# SCH_Line_Following_Robot_PCB_2023-12-15.net
KiCad netlist of a schematic drawn in EasyEDA
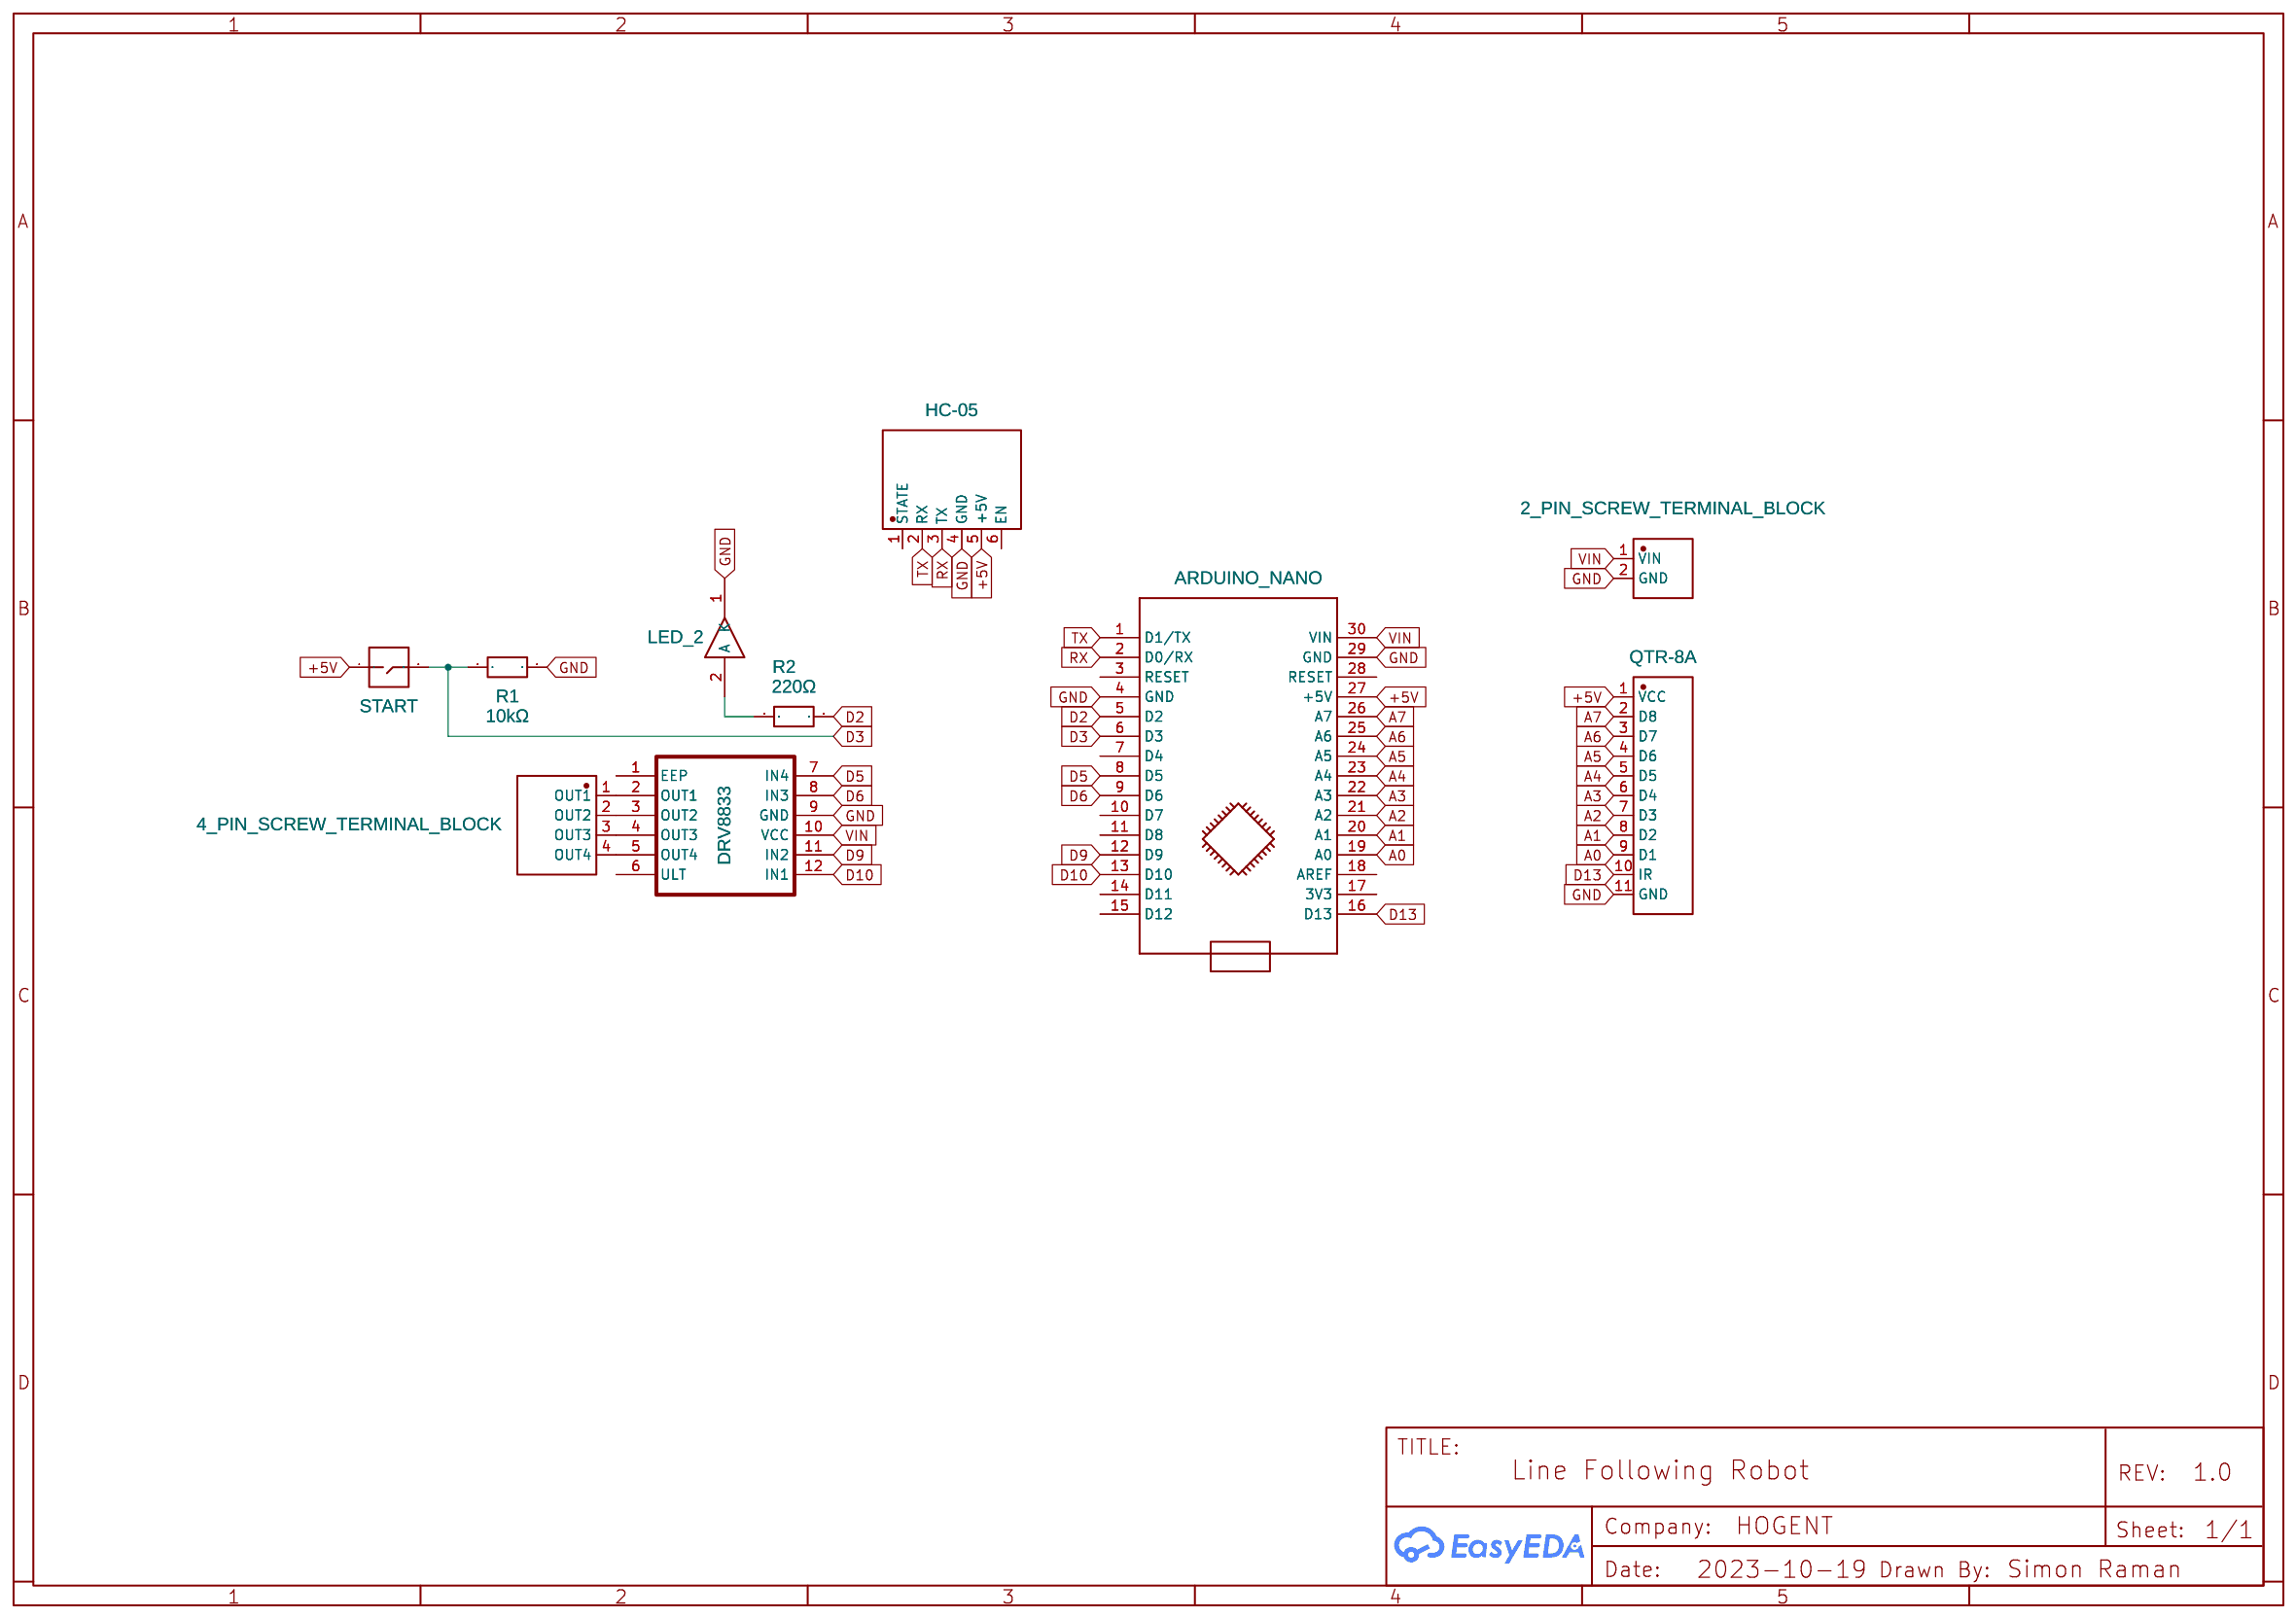
[diagram p0: schematic sheet]

(export (version "E")
  (design (tool "Eeschema 10.0.6"))
  (components
    (comp (ref "2_PIN_SCREW_TERMINAL_BLOCK")
      (value "2 Pin Screw Terminal Block Connector 2.54 mm")
      (libsource (lib "") (part "2 PIN SCREW TERMINAL BLOCK CONNECTOR 2.54 MM"))
    )
    (comp (ref "4_PIN_SCREW_TERMINAL_BLOCK")
      (value "4 PIN SCREW TERMINAL BLOCK CONNECTOR 2.54 MM")
      (libsource (lib "") (part "4 PIN SCREW TERMINAL BLOCK CONNECTOR 2.54 MM"))
    )
    (comp (ref "ARDUINO_NANO")
      (value "ARDUINO NANO CLOCK")
      (fields (field (name "Manufacturer Part") "Arduino-NANO"))
      (libsource (lib "") (part "ARDUINO NANO CLOCK"))
    )
    (comp (ref "DRV8833") (value "DRV8833") (libsource (lib "") (part "DRV8833 12PIN")))
    (comp (ref "HC-05") (value "HC-05") (libsource (lib "") (part "HC-05")))
    (comp (ref "LED_2") (value "led 5 mm") (libsource (lib "") (part "led 5 mm")))
    (comp (ref "QTR-8A") (value "QTR-8A") (libsource (lib "") (part "QTR-8A")))
    (comp (ref "R1")
      (value "10kΩ")
      (libsource (lib "") (part "AXIAL RESISTOR 220 OHM - TH_BD2.3-L6.0-P10.00-D0.4_1"))
    )
    (comp (ref "R2")
      (value "220Ω")
      (libsource (lib "") (part "AXIAL RESISTOR 220 OHM - TH_BD2.3-L6.0-P10.00-D0.4"))
    )
    (comp (ref "START") (value "start") (libsource (lib "") (part "Push Button")))
  )
  (nets
    (net (code "1") (name "+5V") (class "Default")
      (node (ref "ARDUINO_NANO") (pin "27") (pinfunction "+5V_27") (pintype "unspecified"))
      (node (ref "HC-05") (pin "5") (pinfunction "+5V_5") (pintype "unspecified"))
      (node (ref "QTR-8A") (pin "1") (pinfunction "VCC_1") (pintype "unspecified"))
      (node (ref "START") (pin "1") (pinfunction "1_1") (pintype "unspecified"))
    )
    (net (code "2") (name "A0") (class "Default")
      (node (ref "ARDUINO_NANO") (pin "19") (pinfunction "A0_19") (pintype "unspecified"))
      (node (ref "QTR-8A") (pin "9") (pinfunction "D1_9") (pintype "unspecified"))
    )
    (net (code "3") (name "A1") (class "Default")
      (node (ref "ARDUINO_NANO") (pin "20") (pinfunction "A1_20") (pintype "unspecified"))
      (node (ref "QTR-8A") (pin "8") (pinfunction "D2_8") (pintype "unspecified"))
    )
    (net (code "4") (name "A2") (class "Default")
      (node (ref "ARDUINO_NANO") (pin "21") (pinfunction "A2_21") (pintype "unspecified"))
      (node (ref "QTR-8A") (pin "7") (pinfunction "D3_7") (pintype "unspecified"))
    )
    (net (code "5") (name "A3") (class "Default")
      (node (ref "ARDUINO_NANO") (pin "22") (pinfunction "A3_22") (pintype "unspecified"))
      (node (ref "QTR-8A") (pin "6") (pinfunction "D4_6") (pintype "unspecified"))
    )
    (net (code "6") (name "A4") (class "Default")
      (node (ref "ARDUINO_NANO") (pin "23") (pinfunction "A4_23") (pintype "unspecified"))
      (node (ref "QTR-8A") (pin "5") (pinfunction "D5_5") (pintype "unspecified"))
    )
    (net (code "7") (name "A5") (class "Default")
      (node (ref "ARDUINO_NANO") (pin "24") (pinfunction "A5_24") (pintype "unspecified"))
      (node (ref "QTR-8A") (pin "4") (pinfunction "D6_4") (pintype "unspecified"))
    )
    (net (code "8") (name "A6") (class "Default")
      (node (ref "ARDUINO_NANO") (pin "25") (pinfunction "A6_25") (pintype "unspecified"))
      (node (ref "QTR-8A") (pin "3") (pinfunction "D7_3") (pintype "unspecified"))
    )
    (net (code "9") (name "A7") (class "Default")
      (node (ref "ARDUINO_NANO") (pin "26") (pinfunction "A7_26") (pintype "unspecified"))
      (node (ref "QTR-8A") (pin "2") (pinfunction "D8_2") (pintype "unspecified"))
    )
    (net (code "10") (name "D2") (class "Default")
      (node (ref "ARDUINO_NANO") (pin "5") (pinfunction "D2_5") (pintype "unspecified"))
      (node (ref "R2") (pin "2") (pinfunction "2_2") (pintype "unspecified"))
    )
    (net (code "11") (name "D3") (class "Default")
      (node (ref "ARDUINO_NANO") (pin "6") (pinfunction "D3_6") (pintype "unspecified"))
      (node (ref "R1") (pin "2") (pinfunction "2_2") (pintype "unspecified"))
      (node (ref "START") (pin "2") (pinfunction "2_2") (pintype "unspecified"))
    )
    (net (code "12") (name "D5") (class "Default")
      (node (ref "ARDUINO_NANO") (pin "8") (pinfunction "D5_8") (pintype "unspecified"))
      (node (ref "DRV8833") (pin "7") (pinfunction "IN4_7") (pintype "unspecified"))
    )
    (net (code "13") (name "D6") (class "Default")
      (node (ref "ARDUINO_NANO") (pin "9") (pinfunction "D6_9") (pintype "unspecified"))
      (node (ref "DRV8833") (pin "8") (pinfunction "IN3_8") (pintype "unspecified"))
    )
    (net (code "14") (name "D9") (class "Default")
      (node (ref "ARDUINO_NANO") (pin "12") (pinfunction "D9_12") (pintype "unspecified"))
      (node (ref "DRV8833") (pin "11") (pinfunction "IN2_11") (pintype "unspecified"))
    )
    (net (code "15") (name "D10") (class "Default")
      (node (ref "ARDUINO_NANO") (pin "13") (pinfunction "D10_13") (pintype "unspecified"))
      (node (ref "DRV8833") (pin "12") (pinfunction "IN1_12") (pintype "unspecified"))
    )
    (net (code "16") (name "D13") (class "Default")
      (node (ref "ARDUINO_NANO") (pin "16") (pinfunction "D13_16") (pintype "unspecified"))
      (node (ref "QTR-8A") (pin "10") (pinfunction "IR_10") (pintype "unspecified"))
    )
    (net (code "17") (name "GND") (class "Default")
      (node (ref "2_PIN_SCREW_TERMINAL_BLOCK") (pin "2") (pinfunction "GND_2") (pintype "unspecified"))
      (node (ref "ARDUINO_NANO") (pin "29") (pinfunction "GND_29") (pintype "unspecified"))
      (node (ref "ARDUINO_NANO") (pin "4") (pinfunction "GND_4") (pintype "unspecified"))
      (node (ref "DRV8833") (pin "9") (pinfunction "GND_9") (pintype "unspecified"))
      (node (ref "HC-05") (pin "4") (pinfunction "GND_4") (pintype "unspecified"))
      (node (ref "LED_2") (pin "1") (pinfunction "K_1") (pintype "unspecified"))
      (node (ref "QTR-8A") (pin "11") (pinfunction "GND_11") (pintype "unspecified"))
      (node (ref "R1") (pin "1") (pinfunction "1_1") (pintype "unspecified"))
    )
    (net (code "18") (name "Net-(4_PIN_SCREW_TERMINAL_BLOCK-OUT1)") (class "Default")
      (node (ref "4_PIN_SCREW_TERMINAL_BLOCK") (pin "1") (pinfunction "OUT1_1") (pintype "unspecified"))
      (node (ref "DRV8833") (pin "2") (pinfunction "OUT1_2") (pintype "unspecified"))
    )
    (net (code "19") (name "Net-(4_PIN_SCREW_TERMINAL_BLOCK-OUT2)") (class "Default")
      (node (ref "4_PIN_SCREW_TERMINAL_BLOCK") (pin "2") (pinfunction "OUT2_2") (pintype "unspecified"))
      (node (ref "DRV8833") (pin "3") (pinfunction "OUT2_3") (pintype "unspecified"))
    )
    (net (code "20") (name "Net-(4_PIN_SCREW_TERMINAL_BLOCK-OUT3)") (class "Default")
      (node (ref "4_PIN_SCREW_TERMINAL_BLOCK") (pin "3") (pinfunction "OUT3_3") (pintype "unspecified"))
      (node (ref "DRV8833") (pin "4") (pinfunction "OUT3_4") (pintype "unspecified"))
    )
    (net (code "21") (name "Net-(4_PIN_SCREW_TERMINAL_BLOCK-OUT4)") (class "Default")
      (node (ref "4_PIN_SCREW_TERMINAL_BLOCK") (pin "4") (pinfunction "OUT4_4") (pintype "unspecified"))
      (node (ref "DRV8833") (pin "5") (pinfunction "OUT4_5") (pintype "unspecified"))
    )
    (net (code "22") (name "Net-(LED_2-A)") (class "Default")
      (node (ref "LED_2") (pin "2") (pinfunction "A_2") (pintype "unspecified"))
      (node (ref "R2") (pin "1") (pinfunction "1_1") (pintype "unspecified"))
    )
    (net (code "23") (name "RX") (class "Default")
      (node (ref "ARDUINO_NANO") (pin "2") (pinfunction "D0/RX_2") (pintype "unspecified"))
      (node (ref "HC-05") (pin "3") (pinfunction "TX_3") (pintype "unspecified"))
    )
    (net (code "24") (name "TX") (class "Default")
      (node (ref "ARDUINO_NANO") (pin "1") (pinfunction "D1/TX_1") (pintype "unspecified"))
      (node (ref "HC-05") (pin "2") (pinfunction "RX_2") (pintype "unspecified"))
    )
    (net (code "25") (name "VIN") (class "Default")
      (node (ref "2_PIN_SCREW_TERMINAL_BLOCK") (pin "1") (pinfunction "VIN_1") (pintype "unspecified"))
      (node (ref "ARDUINO_NANO") (pin "30") (pinfunction "VIN_30") (pintype "unspecified"))
      (node (ref "DRV8833") (pin "10") (pinfunction "VCC_10") (pintype "unspecified"))
    )
    (net (code "26") (name "unconnected-(ARDUINO_NANO-3V3-Pad17)") (class "Default")
      (node (ref "ARDUINO_NANO") (pin "17") (pinfunction "3V3_17") (pintype "unspecified"))
    )
    (net (code "27") (name "unconnected-(ARDUINO_NANO-AREF-Pad18)") (class "Default")
      (node (ref "ARDUINO_NANO") (pin "18") (pinfunction "AREF_18") (pintype "unspecified"))
    )
    (net (code "28") (name "unconnected-(ARDUINO_NANO-D4-Pad7)") (class "Default")
      (node (ref "ARDUINO_NANO") (pin "7") (pinfunction "D4_7") (pintype "unspecified"))
    )
    (net (code "29") (name "unconnected-(ARDUINO_NANO-D7-Pad10)") (class "Default")
      (node (ref "ARDUINO_NANO") (pin "10") (pinfunction "D7_10") (pintype "unspecified"))
    )
    (net (code "30") (name "unconnected-(ARDUINO_NANO-D8-Pad11)") (class "Default")
      (node (ref "ARDUINO_NANO") (pin "11") (pinfunction "D8_11") (pintype "unspecified"))
    )
    (net (code "31") (name "unconnected-(ARDUINO_NANO-D11-Pad14)") (class "Default")
      (node (ref "ARDUINO_NANO") (pin "14") (pinfunction "D11_14") (pintype "unspecified"))
    )
    (net (code "32") (name "unconnected-(ARDUINO_NANO-D12-Pad15)") (class "Default")
      (node (ref "ARDUINO_NANO") (pin "15") (pinfunction "D12_15") (pintype "unspecified"))
    )
    (net (code "33") (name "unconnected-(ARDUINO_NANO-RESET-Pad3)") (class "Default")
      (node (ref "ARDUINO_NANO") (pin "3") (pinfunction "RESET_3") (pintype "unspecified"))
    )
    (net (code "34") (name "unconnected-(ARDUINO_NANO-RESET-Pad28)") (class "Default")
      (node (ref "ARDUINO_NANO") (pin "28") (pinfunction "RESET_28") (pintype "unspecified"))
    )
    (net (code "35") (name "unconnected-(DRV8833-EEP-Pad1)") (class "Default")
      (node (ref "DRV8833") (pin "1") (pinfunction "EEP_1") (pintype "unspecified"))
    )
    (net (code "36") (name "unconnected-(DRV8833-ULT-Pad6)") (class "Default")
      (node (ref "DRV8833") (pin "6") (pinfunction "ULT_6") (pintype "unspecified"))
    )
    (net (code "37") (name "unconnected-(HC-05-EN-Pad6)") (class "Default")
      (node (ref "HC-05") (pin "6") (pinfunction "EN_6") (pintype "unspecified"))
    )
    (net (code "38") (name "unconnected-(HC-05-STATE-Pad1)") (class "Default")
      (node (ref "HC-05") (pin "1") (pinfunction "STATE_1") (pintype "unspecified"))
    )
  )
)
